# LEDRing.net
KiCad netlist of a schematic drawn in Altium Designer
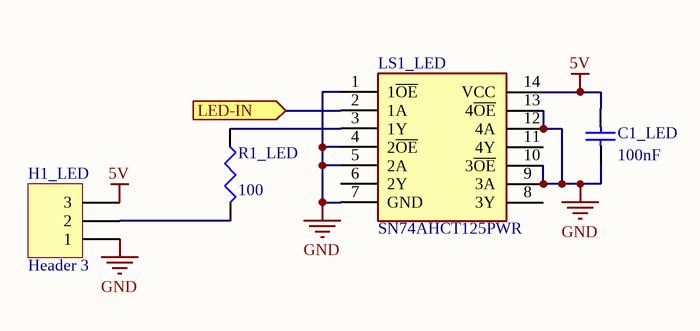
[diagram p0: LEDRing.SchDoc]

(export (version "E")
  (design (tool "Eeschema 10.0.6"))
  (components
    (comp (ref "C1_LED")
      (value "100nF")
      (footprint "1608[0603]")
      (description "Capacitor (Semiconductor SIM Model)")
      (fields (field (name "Comment") "Cap Semi") (field (name "PUBLISHER") "Altium Limited"))
      (libsource (lib "Miscellaneous Devices") (part "Cap Semi"))
    )
    (comp (ref "H1_LED")
      (value "Header 3")
      (footprint "HDR1X3")
      (description "Header, 3-Pin")
      (fields (field (name "PUBLISHER") "Altium Limited"))
      (libsource (lib "Miscellaneous Connectors") (part "Header 3"))
    )
    (comp (ref "LS1_LED")
      (value "SN74AHCT125PWR")
      (footprint "LX1-LEDring:SOP65P640X120-14N")
      (description "Integrated Circuit")
      (fields (field (name "MOUSER PART NUMBER") "595-SN74AHCT125PWR"))
      (libsource (lib "LX1-LEDring") (part "SN74AHCT125PWR"))
    )
    (comp (ref "R1_LED")
      (value "100")
      (footprint "J1-0603")
      (description "Resistor")
      (fields (field (name "Comment") "Res3") (field (name "PUBLISHER") "Altium Limited"))
      (libsource (lib "Miscellaneous Devices") (part "Res3"))
    )
  )
  (nets
    (net (code "1") (name "/LED-IN") (class "Default")
      (node (ref "LS1_LED") (pin "2") (pinfunction "1A_2") (pintype "passive"))
    )
    (net (code "2") (name "5V") (class "Default")
      (node (ref "C1_LED") (pin "2") (pinfunction "2_2") (pintype "passive"))
      (node (ref "H1_LED") (pin "3") (pinfunction "3_3") (pintype "passive"))
      (node (ref "LS1_LED") (pin "14") (pinfunction "VCC_14") (pintype "passive"))
    )
    (net (code "3") (name "GND") (class "Default")
      (node (ref "C1_LED") (pin "1") (pinfunction "1_1") (pintype "passive"))
      (node (ref "H1_LED") (pin "1") (pinfunction "1_1") (pintype "passive"))
      (node (ref "LS1_LED") (pin "1") (pinfunction "1~{OE}_1") (pintype "passive"))
      (node (ref "LS1_LED") (pin "10") (pinfunction "3~{OE}_10") (pintype "passive"))
      (node (ref "LS1_LED") (pin "12") (pinfunction "4A_12") (pintype "passive"))
      (node (ref "LS1_LED") (pin "13") (pinfunction "4~{OE}_13") (pintype "passive"))
      (node (ref "LS1_LED") (pin "4") (pinfunction "2~{OE}_4") (pintype "passive"))
      (node (ref "LS1_LED") (pin "5") (pinfunction "2A_5") (pintype "passive"))
      (node (ref "LS1_LED") (pin "7") (pinfunction "GND_7") (pintype "passive"))
      (node (ref "LS1_LED") (pin "9") (pinfunction "3A_9") (pintype "passive"))
    )
    (net (code "4") (name "Net-(H1_LED-Pad2)") (class "Default")
      (node (ref "H1_LED") (pin "2") (pinfunction "2_2") (pintype "passive"))
      (node (ref "R1_LED") (pin "2") (pinfunction "2_2") (pintype "passive"))
    )
    (net (code "5") (name "Net-(LS1_LED-1Y)") (class "Default")
      (node (ref "LS1_LED") (pin "3") (pinfunction "1Y_3") (pintype "passive"))
      (node (ref "R1_LED") (pin "1") (pinfunction "1_1") (pintype "passive"))
    )
    (net (code "6") (name "unconnected-(LS1_LED-2Y-Pad6)") (class "Default")
      (node (ref "LS1_LED") (pin "6") (pinfunction "2Y_6") (pintype "passive"))
    )
    (net (code "7") (name "unconnected-(LS1_LED-3Y-Pad8)") (class "Default")
      (node (ref "LS1_LED") (pin "8") (pinfunction "3Y_8") (pintype "passive"))
    )
    (net (code "8") (name "unconnected-(LS1_LED-4Y-Pad11)") (class "Default")
      (node (ref "LS1_LED") (pin "11") (pinfunction "4Y_11") (pintype "passive"))
    )
  )
)
